# Jacks_EDCPSU_v5.net
KiCad netlist of a schematic drawn in EAGLE
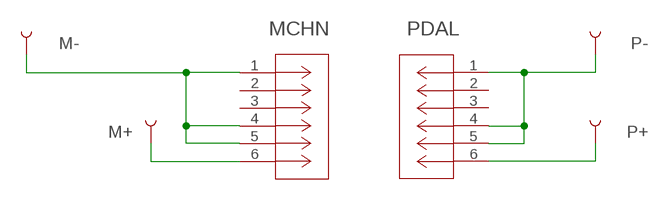
[diagram p0: schematic, sheet 1]

(export (version "E")
  (design (tool "Eeschema 10.0.6"))
  (components
    (comp (ref "M+")
      (value "TEST-POINT3")
      (footprint "eagle-import:PAD.03X.03")
      (libsource (lib "eagle-import") (part "TEST-POINT3"))
    )
    (comp (ref "M-")
      (value "TEST-POINT3")
      (footprint "eagle-import:PAD.03X.03")
      (libsource (lib "eagle-import") (part "TEST-POINT3"))
    )
    (comp (ref "MCHN")
      (value "ACJS-MHDR")
      (footprint "eagle-import:CONN_MHDR_AMP")
      (fields (field (name "COPYRIGHT") "Copyright (C) 2018 Accelerated Designs. All rights reserved"))
      (libsource (lib "eagle-import") (part "ACJS-MHDR"))
    )
    (comp (ref "P+")
      (value "TEST-POINT3")
      (footprint "eagle-import:PAD.03X.03")
      (libsource (lib "eagle-import") (part "TEST-POINT3"))
    )
    (comp (ref "P-")
      (value "TEST-POINT3")
      (footprint "eagle-import:PAD.03X.03")
      (libsource (lib "eagle-import") (part "TEST-POINT3"))
    )
    (comp (ref "PDAL")
      (value "ACJS-MHDR")
      (footprint "eagle-import:CONN_MHDR_AMP")
      (fields (field (name "COPYRIGHT") "Copyright (C) 2018 Accelerated Designs. All rights reserved"))
      (libsource (lib "eagle-import") (part "ACJS-MHDR"))
    )
  )
  (nets
    (net (code "1") (name "Net-(M+-1)") (class "Default")
      (node (ref "M+") (pin "P$1") (pinfunction "1_P$1") (pintype "bidirectional"))
      (node (ref "MCHN") (pin "6") (pinfunction "6_6") (pintype "passive"))
    )
    (net (code "2") (name "Net-(M--1)") (class "Default")
      (node (ref "M-") (pin "P$1") (pinfunction "1_P$1") (pintype "bidirectional"))
      (node (ref "MCHN") (pin "1") (pinfunction "1_1") (pintype "passive"))
      (node (ref "MCHN") (pin "4") (pinfunction "4_4") (pintype "passive"))
      (node (ref "MCHN") (pin "5") (pinfunction "5_5") (pintype "passive"))
    )
    (net (code "3") (name "Net-(P+-1)") (class "Default")
      (node (ref "P+") (pin "P$1") (pinfunction "1_P$1") (pintype "bidirectional"))
      (node (ref "PDAL") (pin "6") (pinfunction "6_6") (pintype "passive"))
    )
    (net (code "4") (name "Net-(P--1)") (class "Default")
      (node (ref "P-") (pin "P$1") (pinfunction "1_P$1") (pintype "bidirectional"))
      (node (ref "PDAL") (pin "1") (pinfunction "1_1") (pintype "passive"))
      (node (ref "PDAL") (pin "4") (pinfunction "4_4") (pintype "passive"))
      (node (ref "PDAL") (pin "5") (pinfunction "5_5") (pintype "passive"))
    )
    (net (code "5") (name "unconnected-(MCHN-Pad2)") (class "Default")
      (node (ref "MCHN") (pin "2") (pinfunction "2_2") (pintype "passive"))
    )
    (net (code "6") (name "unconnected-(MCHN-Pad3)") (class "Default")
      (node (ref "MCHN") (pin "3") (pinfunction "3_3") (pintype "passive"))
    )
    (net (code "7") (name "unconnected-(PDAL-Pad2)") (class "Default")
      (node (ref "PDAL") (pin "2") (pinfunction "2_2") (pintype "passive"))
    )
    (net (code "8") (name "unconnected-(PDAL-Pad3)") (class "Default")
      (node (ref "PDAL") (pin "3") (pinfunction "3_3") (pintype "passive"))
    )
  )
)
